# Catch_The_Light_Game.net
KiCad netlist of a schematic drawn in EAGLE
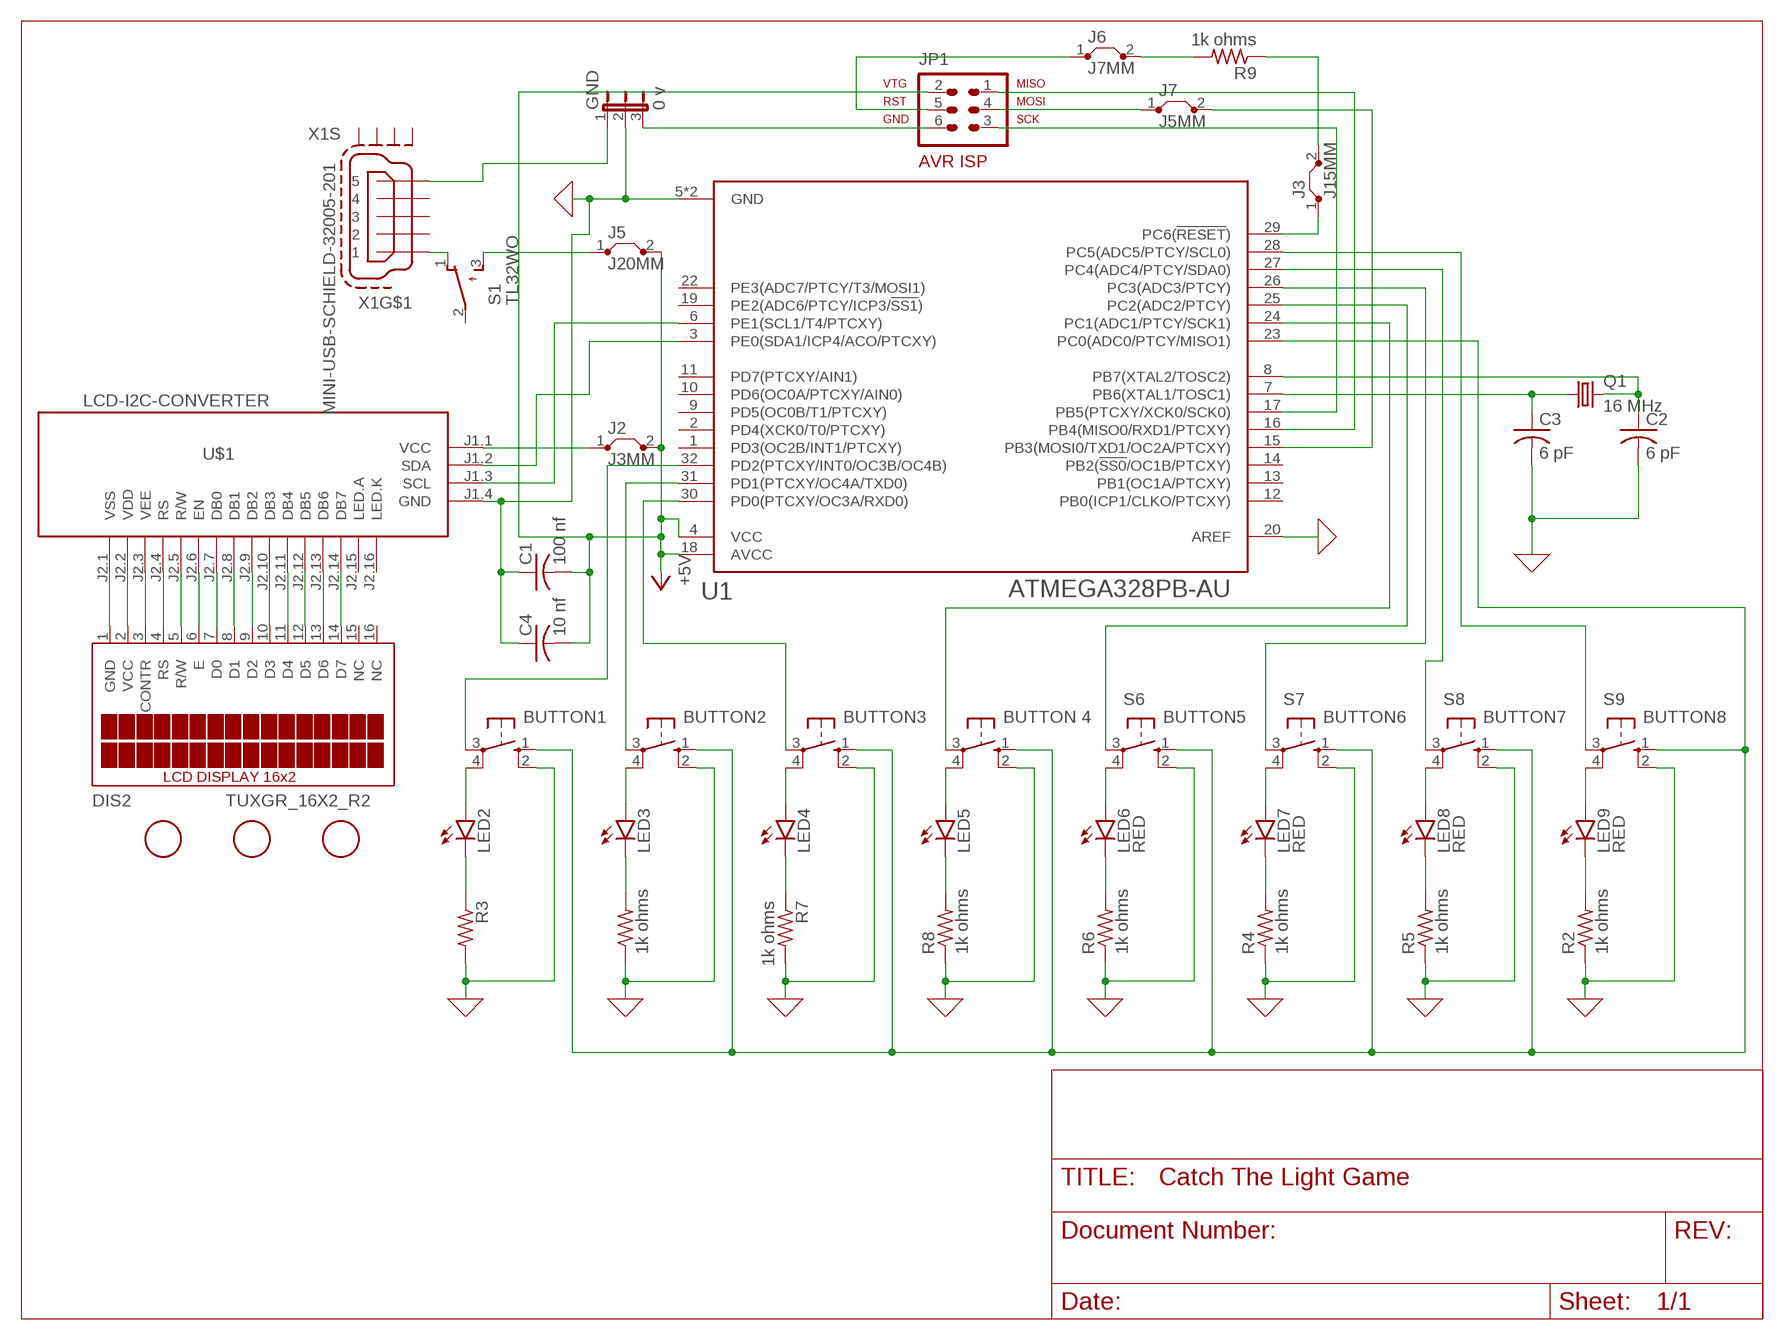
[diagram p0: schematic, sheet 1]

(export (version "E")
  (design (tool "Eeschema 10.0.6"))
  (components
    (comp (ref "C1")
      (value "100 nf")
      (footprint "eagle-import:C025-024X044")
      (libsource (lib "eagle-import") (part "C-US025-024X044"))
    )
    (comp (ref "C2")
      (value "6 pF")
      (footprint "eagle-import:C025-024X044")
      (libsource (lib "eagle-import") (part "C-US025-024X044"))
    )
    (comp (ref "C3")
      (value "6 pF")
      (footprint "eagle-import:C025-024X044")
      (libsource (lib "eagle-import") (part "C-US025-024X044"))
    )
    (comp (ref "C4")
      (value "10 nf")
      (footprint "eagle-import:C025-024X044")
      (libsource (lib "eagle-import") (part "C-US025-024X044"))
    )
    (comp (ref "DIS2")
      (value "TUXGR_16X2_R2")
      (footprint "eagle-import:TUXGR_16X2_R2")
      (fields (field (name "SPICEPREFIX") "X"))
      (libsource (lib "eagle-import") (part "TUXGR_16X2_R2"))
    )
    (comp (ref "GND")
      (value "0 v")
      (footprint "eagle-import:JP2")
      (libsource (lib "eagle-import") (part "JP2E"))
    )
    (comp (ref "J2")
      (value "J3MM")
      (footprint "eagle-import:03")
      (libsource (lib "eagle-import") (part "J3MM"))
    )
    (comp (ref "J3")
      (value "J15MM")
      (footprint "eagle-import:15")
      (libsource (lib "eagle-import") (part "jumper_252_J15MM"))
    )
    (comp (ref "J5")
      (value "J20MM")
      (footprint "eagle-import:20")
      (libsource (lib "eagle-import") (part "jumper_252_J20MM"))
    )
    (comp (ref "J6")
      (value "J7MM")
      (footprint "eagle-import:07")
      (libsource (lib "eagle-import") (part "jumper_252_J7MM"))
    )
    (comp (ref "J7")
      (value "J5MM")
      (footprint "eagle-import:05")
      (libsource (lib "eagle-import") (part "jumper_252_J5MM"))
    )
    (comp (ref "JP1")
      (value "AVR-ISP-6R")
      (footprint "eagle-import:AVR-ISP-6R")
      (libsource (lib "eagle-import") (part "AVR-ISP-6R"))
    )
    (comp (ref "LED2")
      (value "RED")
      (footprint "eagle-import:LED5MM")
      (libsource (lib "eagle-import") (part "LED5MM"))
    )
    (comp (ref "LED3")
      (value "RED")
      (footprint "eagle-import:LED5MM")
      (libsource (lib "eagle-import") (part "LED5MM"))
    )
    (comp (ref "LED4")
      (value "RED")
      (footprint "eagle-import:LED5MM")
      (libsource (lib "eagle-import") (part "LED5MM"))
    )
    (comp (ref "LED5")
      (value "RED")
      (footprint "eagle-import:LED5MM")
      (libsource (lib "eagle-import") (part "LED5MM"))
    )
    (comp (ref "LED6")
      (value "RED")
      (footprint "eagle-import:LED5MM")
      (libsource (lib "eagle-import") (part "LED5MM"))
    )
    (comp (ref "LED7")
      (value "RED")
      (footprint "eagle-import:LED5MM")
      (libsource (lib "eagle-import") (part "LED5MM"))
    )
    (comp (ref "LED8")
      (value "RED")
      (footprint "eagle-import:LED5MM")
      (libsource (lib "eagle-import") (part "LED5MM"))
    )
    (comp (ref "LED9")
      (value "RED")
      (footprint "eagle-import:LED5MM")
      (libsource (lib "eagle-import") (part "LED5MM"))
    )
    (comp (ref "Q1")
      (value "16 MHz")
      (footprint "eagle-import:HC49_S")
      (libsource (lib "eagle-import") (part "CRYSTALHC49S"))
    )
    (comp (ref "R1")
      (value "1k ohms")
      (footprint "eagle-import:0204_5")
      (libsource (lib "eagle-import") (part "R-US_0204/5"))
    )
    (comp (ref "R2")
      (value "1k ohms")
      (footprint "eagle-import:0204_5")
      (libsource (lib "eagle-import") (part "R-US_0204/5"))
    )
    (comp (ref "R3")
      (value "1K ohms")
      (footprint "eagle-import:0204_5")
      (libsource (lib "eagle-import") (part "R-US_0204/5"))
    )
    (comp (ref "R4")
      (value "1k ohms")
      (footprint "eagle-import:0204_5")
      (libsource (lib "eagle-import") (part "R-US_0204/5"))
    )
    (comp (ref "R5")
      (value "1k ohms")
      (footprint "eagle-import:0204_5")
      (libsource (lib "eagle-import") (part "R-US_0204/5"))
    )
    (comp (ref "R6")
      (value "1k ohms")
      (footprint "eagle-import:0204_5")
      (libsource (lib "eagle-import") (part "R-US_0204/5"))
    )
    (comp (ref "R7")
      (value "1k ohms")
      (footprint "eagle-import:0204_5")
      (libsource (lib "eagle-import") (part "R-US_0204/5"))
    )
    (comp (ref "R8")
      (value "1k ohms")
      (footprint "eagle-import:0204_5")
      (libsource (lib "eagle-import") (part "R-US_0204/5"))
    )
    (comp (ref "R9")
      (value "1k ohms")
      (footprint "eagle-import:0204_5")
      (libsource (lib "eagle-import") (part "R-US_0204/5"))
    )
    (comp (ref "S1")
      (value "TL32WO")
      (footprint "eagle-import:TL3XWO")
      (libsource (lib "eagle-import") (part "TL32WO"))
    )
    (comp (ref "S2")
      (value "BUTTON1")
      (footprint "eagle-import:B3F-10XX")
      (fields (field (name "MPN") "B3F-1000"))
      (libsource (lib "eagle-import") (part "10-XX"))
    )
    (comp (ref "S3")
      (value "BUTTON2")
      (footprint "eagle-import:B3F-10XX")
      (fields (field (name "MPN") "B3F-1000"))
      (libsource (lib "eagle-import") (part "10-XX"))
    )
    (comp (ref "S4")
      (value "BUTTON3")
      (footprint "eagle-import:B3F-10XX")
      (fields (field (name "MPN") "B3F-1000"))
      (libsource (lib "eagle-import") (part "10-XX"))
    )
    (comp (ref "S5")
      (value "BUTTON 4")
      (footprint "eagle-import:B3F-10XX")
      (fields (field (name "MPN") "B3F-1000"))
      (libsource (lib "eagle-import") (part "10-XX"))
    )
    (comp (ref "S6")
      (value "BUTTON5")
      (footprint "eagle-import:B3F-10XX")
      (fields (field (name "MPN") "B3F-1000"))
      (libsource (lib "eagle-import") (part "10-XX"))
    )
    (comp (ref "S7")
      (value "BUTTON6")
      (footprint "eagle-import:B3F-10XX")
      (fields (field (name "MPN") "B3F-1000"))
      (libsource (lib "eagle-import") (part "10-XX"))
    )
    (comp (ref "S8")
      (value "BUTTON7")
      (footprint "eagle-import:B3F-10XX")
      (fields (field (name "MPN") "B3F-1000"))
      (libsource (lib "eagle-import") (part "10-XX"))
    )
    (comp (ref "S9")
      (value "BUTTON8")
      (footprint "eagle-import:B3F-10XX")
      (fields (field (name "MPN") "B3F-1000"))
      (libsource (lib "eagle-import") (part "10-XX"))
    )
    (comp (ref "U$1")
      (value "LCD-I2C-CONVERTER")
      (footprint "eagle-import:LCD-I2C-CONVERTER")
      (fields (field (name "SPICEPREFIX") "X"))
      (libsource (lib "eagle-import") (part "LCD-I2C-CONVERTER"))
    )
    (comp (ref "U$2")
      (value "FIDUCIAL")
      (footprint "eagle-import:FIDUCIAL_1MM")
      (libsource (lib "eagle-import") (part "FIDUCIAL"))
    )
    (comp (ref "U$3")
      (value "FIDUCIAL")
      (footprint "eagle-import:FIDUCIAL_1MM")
      (libsource (lib "eagle-import") (part "FIDUCIAL"))
    )
    (comp (ref "U$4")
      (value "FIDUCIAL")
      (footprint "eagle-import:FIDUCIAL_1MM")
      (libsource (lib "eagle-import") (part "FIDUCIAL"))
    )
    (comp (ref "U1")
      (value "ATMEGA328PB-AU")
      (footprint "eagle-import:QFP80P900X900X120-32N")
      (fields (field (name "MF") "Microchip Technology"))
      (libsource (lib "eagle-import") (part "ATMEGA328PB-AU"))
    )
    (comp (ref "X1")
      (value "MINI-USB-SCHIELD-32005-201")
      (footprint "eagle-import:32005-201")
      (libsource (lib "eagle-import") (part "MINI-USB-SCHIELD-32005-201"))
    )
  )
  (nets
    (net (code "1") (name "+5V") (class "Default")
      (node (ref "C1") (pin "2") (pinfunction "2_2") (pintype "passive"))
      (node (ref "C4") (pin "2") (pinfunction "2_2") (pintype "passive"))
      (node (ref "J2") (pin "2") (pinfunction "2_2") (pintype "passive"))
      (node (ref "J5") (pin "2") (pinfunction "2_2") (pintype "passive"))
      (node (ref "JP1") (pin "2") (pinfunction "2_2") (pintype "passive"))
      (node (ref "U1") (pin "18") (pinfunction "AVCC_18") (pintype "power_in"))
      (node (ref "U1") (pin "4") (pinfunction "VCC_4") (pintype "power_in"))
    )
    (net (code "2") (name "GND") (class "Default")
      (node (ref "C1") (pin "1") (pinfunction "1_1") (pintype "passive"))
      (node (ref "C2") (pin "2") (pinfunction "2_2") (pintype "passive"))
      (node (ref "C3") (pin "2") (pinfunction "2_2") (pintype "passive"))
      (node (ref "C4") (pin "1") (pinfunction "1_1") (pintype "passive"))
      (node (ref "GND") (pin "2") (pinfunction "2_2") (pintype "passive"))
      (node (ref "R1") (pin "1") (pinfunction "1_1") (pintype "passive"))
      (node (ref "R2") (pin "1") (pinfunction "1_1") (pintype "passive"))
      (node (ref "R3") (pin "2") (pinfunction "2_2") (pintype "passive"))
      (node (ref "R4") (pin "1") (pinfunction "1_1") (pintype "passive"))
      (node (ref "R5") (pin "1") (pinfunction "1_1") (pintype "passive"))
      (node (ref "R6") (pin "1") (pinfunction "1_1") (pintype "passive"))
      (node (ref "R7") (pin "2") (pinfunction "2_2") (pintype "passive"))
      (node (ref "R8") (pin "1") (pinfunction "1_1") (pintype "passive"))
      (node (ref "S2") (pin "2") (pinfunction "S1_2") (pintype "passive"))
      (node (ref "S3") (pin "2") (pinfunction "S1_2") (pintype "passive"))
      (node (ref "S4") (pin "2") (pinfunction "S1_2") (pintype "passive"))
      (node (ref "S5") (pin "2") (pinfunction "S1_2") (pintype "passive"))
      (node (ref "S6") (pin "2") (pinfunction "S1_2") (pintype "passive"))
      (node (ref "S7") (pin "2") (pinfunction "S1_2") (pintype "passive"))
      (node (ref "S8") (pin "2") (pinfunction "S1_2") (pintype "passive"))
      (node (ref "S9") (pin "2") (pinfunction "S1_2") (pintype "passive"))
      (node (ref "U$1") (pin "J1.4") (pinfunction "GND_J1.4") (pintype "power_in"))
      (node (ref "U1") (pin "20") (pinfunction "AREF_20") (pintype "input"))
      (node (ref "U1") (pin "21") (pinfunction "GND_21") (pintype "power_in"))
      (node (ref "U1") (pin "5") (pinfunction "GND_5") (pintype "power_in"))
    )
    (net (code "3") (name "Net-(DIS2-CONTR)") (class "Default")
      (node (ref "DIS2") (pin "3") (pinfunction "CONTR_3") (pintype "input"))
      (node (ref "U$1") (pin "J2.3") (pinfunction "VEE_J2.3") (pintype "bidirectional"))
    )
    (net (code "4") (name "Net-(DIS2-D0)") (class "Default")
      (node (ref "DIS2") (pin "7") (pinfunction "D0_7") (pintype "input"))
      (node (ref "U$1") (pin "J2.7") (pinfunction "DB0_J2.7") (pintype "bidirectional"))
    )
    (net (code "5") (name "Net-(DIS2-D1)") (class "Default")
      (node (ref "DIS2") (pin "8") (pinfunction "D1_8") (pintype "input"))
      (node (ref "U$1") (pin "J2.8") (pinfunction "DB1_J2.8") (pintype "bidirectional"))
    )
    (net (code "6") (name "Net-(DIS2-D2)") (class "Default")
      (node (ref "DIS2") (pin "9") (pinfunction "D2_9") (pintype "input"))
      (node (ref "U$1") (pin "J2.9") (pinfunction "DB2_J2.9") (pintype "bidirectional"))
    )
    (net (code "7") (name "Net-(DIS2-D3)") (class "Default")
      (node (ref "DIS2") (pin "10") (pinfunction "D3_10") (pintype "input"))
      (node (ref "U$1") (pin "J2.10") (pinfunction "DB3_J2.10") (pintype "bidirectional"))
    )
    (net (code "8") (name "Net-(DIS2-D4)") (class "Default")
      (node (ref "DIS2") (pin "11") (pinfunction "D4_11") (pintype "input"))
      (node (ref "U$1") (pin "J2.11") (pinfunction "DB4_J2.11") (pintype "bidirectional"))
    )
    (net (code "9") (name "Net-(DIS2-D5)") (class "Default")
      (node (ref "DIS2") (pin "12") (pinfunction "D5_12") (pintype "input"))
      (node (ref "U$1") (pin "J2.12") (pinfunction "DB5_J2.12") (pintype "bidirectional"))
    )
    (net (code "10") (name "Net-(DIS2-D6)") (class "Default")
      (node (ref "DIS2") (pin "13") (pinfunction "D6_13") (pintype "input"))
      (node (ref "U$1") (pin "J2.13") (pinfunction "DB6_J2.13") (pintype "bidirectional"))
    )
    (net (code "11") (name "Net-(DIS2-D7)") (class "Default")
      (node (ref "DIS2") (pin "14") (pinfunction "D7_14") (pintype "input"))
      (node (ref "U$1") (pin "J2.14") (pinfunction "DB7_J2.14") (pintype "bidirectional"))
    )
    (net (code "12") (name "Net-(DIS2-E)") (class "Default")
      (node (ref "DIS2") (pin "6") (pinfunction "E_6") (pintype "input"))
      (node (ref "U$1") (pin "J2.6") (pinfunction "EN_J2.6") (pintype "bidirectional"))
    )
    (net (code "13") (name "Net-(DIS2-GND)") (class "Default")
      (node (ref "DIS2") (pin "1") (pinfunction "GND_1") (pintype "power_in"))
      (node (ref "U$1") (pin "J2.1") (pinfunction "VSS_J2.1") (pintype "bidirectional"))
    )
    (net (code "14") (name "Net-(DIS2-RS)") (class "Default")
      (node (ref "DIS2") (pin "4") (pinfunction "RS_4") (pintype "input"))
      (node (ref "U$1") (pin "J2.4") (pinfunction "RS_J2.4") (pintype "bidirectional"))
    )
    (net (code "15") (name "Net-(DIS2-R{slash}W)") (class "Default")
      (node (ref "DIS2") (pin "5") (pinfunction "R/W_5") (pintype "input"))
      (node (ref "U$1") (pin "J2.5") (pinfunction "R/W_J2.5") (pintype "bidirectional"))
    )
    (net (code "16") (name "Net-(DIS2-VCC)") (class "Default")
      (node (ref "DIS2") (pin "2") (pinfunction "VCC_2") (pintype "power_in"))
      (node (ref "U$1") (pin "J2.2") (pinfunction "VDD_J2.2") (pintype "bidirectional"))
    )
    (net (code "17") (name "Net-(GND-Pad1)") (class "Default")
      (node (ref "GND") (pin "1") (pinfunction "1_1") (pintype "passive"))
      (node (ref "X1") (pin "5") (pinfunction "5_5") (pintype "passive"))
    )
    (net (code "18") (name "Net-(GND-Pad3)") (class "Default")
      (node (ref "GND") (pin "3") (pinfunction "3_3") (pintype "passive"))
      (node (ref "JP1") (pin "6") (pinfunction "6_6") (pintype "passive"))
    )
    (net (code "19") (name "Net-(J3-Pad2)") (class "Default")
      (node (ref "J3") (pin "2") (pinfunction "2_2") (pintype "passive"))
      (node (ref "R9") (pin "1") (pinfunction "1_1") (pintype "passive"))
    )
    (net (code "20") (name "Net-(J6-Pad1)") (class "Default")
      (node (ref "J6") (pin "1") (pinfunction "1_1") (pintype "passive"))
      (node (ref "JP1") (pin "5") (pinfunction "5_5") (pintype "passive"))
    )
    (net (code "21") (name "Net-(J6-Pad2)") (class "Default")
      (node (ref "J6") (pin "2") (pinfunction "2_2") (pintype "passive"))
      (node (ref "R9") (pin "2") (pinfunction "2_2") (pintype "passive"))
    )
    (net (code "22") (name "Net-(J7-Pad1)") (class "Default")
      (node (ref "J7") (pin "1") (pinfunction "1_1") (pintype "passive"))
      (node (ref "JP1") (pin "4") (pinfunction "4_4") (pintype "passive"))
    )
    (net (code "23") (name "Net-(LED2-C)") (class "Default")
      (node (ref "LED2") (pin "K") (pinfunction "C_K") (pintype "passive"))
      (node (ref "R3") (pin "1") (pinfunction "1_1") (pintype "passive"))
    )
    (net (code "24") (name "Net-(LED3-C)") (class "Default")
      (node (ref "LED3") (pin "K") (pinfunction "C_K") (pintype "passive"))
      (node (ref "R1") (pin "2") (pinfunction "2_2") (pintype "passive"))
    )
    (net (code "25") (name "Net-(LED4-C)") (class "Default")
      (node (ref "LED4") (pin "K") (pinfunction "C_K") (pintype "passive"))
      (node (ref "R7") (pin "1") (pinfunction "1_1") (pintype "passive"))
    )
    (net (code "26") (name "Net-(LED5-C)") (class "Default")
      (node (ref "LED5") (pin "K") (pinfunction "C_K") (pintype "passive"))
      (node (ref "R8") (pin "2") (pinfunction "2_2") (pintype "passive"))
    )
    (net (code "27") (name "Net-(LED6-C)") (class "Default")
      (node (ref "LED6") (pin "K") (pinfunction "C_K") (pintype "passive"))
      (node (ref "R6") (pin "2") (pinfunction "2_2") (pintype "passive"))
    )
    (net (code "28") (name "Net-(LED7-C)") (class "Default")
      (node (ref "LED7") (pin "K") (pinfunction "C_K") (pintype "passive"))
      (node (ref "R4") (pin "2") (pinfunction "2_2") (pintype "passive"))
    )
    (net (code "29") (name "Net-(LED8-C)") (class "Default")
      (node (ref "LED8") (pin "K") (pinfunction "C_K") (pintype "passive"))
      (node (ref "R5") (pin "2") (pinfunction "2_2") (pintype "passive"))
    )
    (net (code "30") (name "Net-(LED9-C)") (class "Default")
      (node (ref "LED9") (pin "K") (pinfunction "C_K") (pintype "passive"))
      (node (ref "R2") (pin "2") (pinfunction "2_2") (pintype "passive"))
    )
    (net (code "31") (name "Net-(S1-O)") (class "Default")
      (node (ref "S1") (pin "1") (pinfunction "O_1") (pintype "passive"))
      (node (ref "X1") (pin "1") (pinfunction "1_1") (pintype "passive"))
    )
    (net (code "32") (name "Net-(S1-S)") (class "Default")
      (node (ref "J5") (pin "1") (pinfunction "1_1") (pintype "passive"))
      (node (ref "S1") (pin "3") (pinfunction "S_3") (pintype "passive"))
    )
    (net (code "33") (name "Net-(S2-P)") (class "Default")
      (node (ref "S2") (pin "3") (pinfunction "P_3") (pintype "passive"))
      (node (ref "U1") (pin "32") (pinfunction "PD2(PTCXY/INT0/OC3B/OC4B)_32") (pintype "bidirectional"))
    )
    (net (code "34") (name "Net-(S2-P1)") (class "Default")
      (node (ref "LED2") (pin "A") (pinfunction "A_A") (pintype "passive"))
      (node (ref "S2") (pin "4") (pinfunction "P1_4") (pintype "passive"))
    )
    (net (code "35") (name "Net-(S2-S)") (class "Default")
      (node (ref "S2") (pin "1") (pinfunction "S_1") (pintype "passive"))
      (node (ref "S3") (pin "1") (pinfunction "S_1") (pintype "passive"))
      (node (ref "S4") (pin "1") (pinfunction "S_1") (pintype "passive"))
      (node (ref "S5") (pin "1") (pinfunction "S_1") (pintype "passive"))
      (node (ref "S6") (pin "1") (pinfunction "S_1") (pintype "passive"))
      (node (ref "S7") (pin "1") (pinfunction "S_1") (pintype "passive"))
      (node (ref "S8") (pin "1") (pinfunction "S_1") (pintype "passive"))
      (node (ref "S9") (pin "1") (pinfunction "S_1") (pintype "passive"))
      (node (ref "U1") (pin "23") (pinfunction "PC0(ADC0/PTCY/MISO1)_23") (pintype "bidirectional"))
    )
    (net (code "36") (name "Net-(S3-P)") (class "Default")
      (node (ref "S3") (pin "3") (pinfunction "P_3") (pintype "passive"))
      (node (ref "U1") (pin "31") (pinfunction "PD1(PTCXY/OC4A/TXD0)_31") (pintype "bidirectional"))
    )
    (net (code "37") (name "Net-(S3-P1)") (class "Default")
      (node (ref "LED3") (pin "A") (pinfunction "A_A") (pintype "passive"))
      (node (ref "S3") (pin "4") (pinfunction "P1_4") (pintype "passive"))
    )
    (net (code "38") (name "Net-(S4-P)") (class "Default")
      (node (ref "S4") (pin "3") (pinfunction "P_3") (pintype "passive"))
      (node (ref "U1") (pin "30") (pinfunction "PD0(PTCXY/OC3A/RXD0)_30") (pintype "bidirectional"))
    )
    (net (code "39") (name "Net-(S4-P1)") (class "Default")
      (node (ref "LED4") (pin "A") (pinfunction "A_A") (pintype "passive"))
      (node (ref "S4") (pin "4") (pinfunction "P1_4") (pintype "passive"))
    )
    (net (code "40") (name "Net-(S5-P)") (class "Default")
      (node (ref "S5") (pin "3") (pinfunction "P_3") (pintype "passive"))
      (node (ref "U1") (pin "24") (pinfunction "PC1(ADC1/PTCY/SCK1)_24") (pintype "bidirectional"))
    )
    (net (code "41") (name "Net-(S5-P1)") (class "Default")
      (node (ref "LED5") (pin "A") (pinfunction "A_A") (pintype "passive"))
      (node (ref "S5") (pin "4") (pinfunction "P1_4") (pintype "passive"))
    )
    (net (code "42") (name "Net-(S6-P)") (class "Default")
      (node (ref "S6") (pin "3") (pinfunction "P_3") (pintype "passive"))
      (node (ref "U1") (pin "25") (pinfunction "PC2(ADC2/PTCY)_25") (pintype "bidirectional"))
    )
    (net (code "43") (name "Net-(S6-P1)") (class "Default")
      (node (ref "LED6") (pin "A") (pinfunction "A_A") (pintype "passive"))
      (node (ref "S6") (pin "4") (pinfunction "P1_4") (pintype "passive"))
    )
    (net (code "44") (name "Net-(S7-P)") (class "Default")
      (node (ref "S7") (pin "3") (pinfunction "P_3") (pintype "passive"))
      (node (ref "U1") (pin "26") (pinfunction "PC3(ADC3/PTCY)_26") (pintype "bidirectional"))
    )
    (net (code "45") (name "Net-(S7-P1)") (class "Default")
      (node (ref "LED7") (pin "A") (pinfunction "A_A") (pintype "passive"))
      (node (ref "S7") (pin "4") (pinfunction "P1_4") (pintype "passive"))
    )
    (net (code "46") (name "Net-(S8-P)") (class "Default")
      (node (ref "S8") (pin "3") (pinfunction "P_3") (pintype "passive"))
      (node (ref "U1") (pin "27") (pinfunction "PC4(ADC4/PTCY/SDA0)_27") (pintype "bidirectional"))
    )
    (net (code "47") (name "Net-(S8-P1)") (class "Default")
      (node (ref "LED8") (pin "A") (pinfunction "A_A") (pintype "passive"))
      (node (ref "S8") (pin "4") (pinfunction "P1_4") (pintype "passive"))
    )
    (net (code "48") (name "Net-(S9-P)") (class "Default")
      (node (ref "S9") (pin "3") (pinfunction "P_3") (pintype "passive"))
      (node (ref "U1") (pin "28") (pinfunction "PC5(ADC5/PTCY/SCL0)_28") (pintype "bidirectional"))
    )
    (net (code "49") (name "Net-(S9-P1)") (class "Default")
      (node (ref "LED9") (pin "A") (pinfunction "A_A") (pintype "passive"))
      (node (ref "S9") (pin "4") (pinfunction "P1_4") (pintype "passive"))
    )
    (net (code "50") (name "Net-(U$1-SCL)") (class "Default")
      (node (ref "U$1") (pin "J1.3") (pinfunction "SCL_J1.3") (pintype "bidirectional"))
      (node (ref "U1") (pin "6") (pinfunction "PE1(SCL1/T4/PTCXY)_6") (pintype "bidirectional"))
    )
    (net (code "51") (name "Net-(U$1-SDA)") (class "Default")
      (node (ref "U$1") (pin "J1.2") (pinfunction "SDA_J1.2") (pintype "bidirectional"))
      (node (ref "U1") (pin "3") (pinfunction "PE0(SDA1/ICP4/ACO/PTCXY)_3") (pintype "bidirectional"))
    )
    (net (code "52") (name "Net-(U$1-VCC)") (class "Default")
      (node (ref "J2") (pin "1") (pinfunction "1_1") (pintype "passive"))
      (node (ref "U$1") (pin "J1.1") (pinfunction "VCC_J1.1") (pintype "power_in"))
    )
    (net (code "53") (name "Net-(U1-PB3(MOSI0{slash}TXD1{slash}OC2A{slash}PTCXY))") (class "Default")
      (node (ref "J7") (pin "2") (pinfunction "2_2") (pintype "passive"))
      (node (ref "U1") (pin "15") (pinfunction "PB3(MOSI0/TXD1/OC2A/PTCXY)_15") (pintype "bidirectional"))
    )
    (net (code "54") (name "Net-(U1-PB4(MISO0{slash}RXD1{slash}PTCXY))") (class "Default")
      (node (ref "JP1") (pin "1") (pinfunction "1_1") (pintype "passive"))
      (node (ref "U1") (pin "16") (pinfunction "PB4(MISO0/RXD1/PTCXY)_16") (pintype "bidirectional"))
    )
    (net (code "55") (name "Net-(U1-PB5(PTCXY{slash}XCK0{slash}SCK0))") (class "Default")
      (node (ref "JP1") (pin "3") (pinfunction "3_3") (pintype "passive"))
      (node (ref "U1") (pin "17") (pinfunction "PB5(PTCXY/XCK0/SCK0)_17") (pintype "bidirectional"))
    )
    (net (code "56") (name "Net-(U1-PB6(XTAL1{slash}TOSC1))") (class "Default")
      (node (ref "C3") (pin "1") (pinfunction "1_1") (pintype "passive"))
      (node (ref "Q1") (pin "1") (pinfunction "1_1") (pintype "passive"))
      (node (ref "U1") (pin "7") (pinfunction "PB6(XTAL1/TOSC1)_7") (pintype "bidirectional"))
    )
    (net (code "57") (name "Net-(U1-PB7(XTAL2{slash}TOSC2))") (class "Default")
      (node (ref "C2") (pin "1") (pinfunction "1_1") (pintype "passive"))
      (node (ref "Q1") (pin "2") (pinfunction "2_2") (pintype "passive"))
      (node (ref "U1") (pin "8") (pinfunction "PB7(XTAL2/TOSC2)_8") (pintype "bidirectional"))
    )
    (net (code "58") (name "Net-(U1-PC6(~{RESET}))") (class "Default")
      (node (ref "J3") (pin "1") (pinfunction "1_1") (pintype "passive"))
      (node (ref "U1") (pin "29") (pinfunction "PC6(~{RESET})_29") (pintype "bidirectional"))
    )
    (net (code "59") (name "unconnected-(DIS2-NC-Pad15)") (class "Default")
      (node (ref "DIS2") (pin "15") (pinfunction "NC_15") (pintype "no_connect"))
    )
    (net (code "60") (name "unconnected-(DIS2-NC-Pad16)") (class "Default")
      (node (ref "DIS2") (pin "16") (pinfunction "NC_16") (pintype "no_connect"))
    )
    (net (code "61") (name "unconnected-(S1-P-Pad2)") (class "Default")
      (node (ref "S1") (pin "2") (pinfunction "P_2") (pintype "passive"))
    )
    (net (code "62") (name "unconnected-(U$1-LED.A-PadJ2.15)") (class "Default")
      (node (ref "U$1") (pin "J2.15") (pinfunction "LED.A_J2.15") (pintype "bidirectional"))
    )
    (net (code "63") (name "unconnected-(U$1-LED.K-PadJ2.16)") (class "Default")
      (node (ref "U$1") (pin "J2.16") (pinfunction "LED.K_J2.16") (pintype "bidirectional"))
    )
    (net (code "64") (name "unconnected-(U1-PB0(ICP1{slash}CLKO{slash}PTCXY)-Pad12)") (class "Default")
      (node (ref "U1") (pin "12") (pinfunction "PB0(ICP1/CLKO/PTCXY)_12") (pintype "bidirectional"))
    )
    (net (code "65") (name "unconnected-(U1-PB1(OC1A{slash}PTCXY)-Pad13)") (class "Default")
      (node (ref "U1") (pin "13") (pinfunction "PB1(OC1A/PTCXY)_13") (pintype "bidirectional"))
    )
    (net (code "66") (name "unconnected-(U1-PB2(~{SS0}{slash}OC1B{slash}PTCXY)-Pad14)") (class "Default")
      (node (ref "U1") (pin "14") (pinfunction "PB2(~{SS0}/OC1B/PTCXY)_14") (pintype "bidirectional"))
    )
    (net (code "67") (name "unconnected-(U1-PD3(OC2B{slash}INT1{slash}PTCXY)-Pad1)") (class "Default")
      (node (ref "U1") (pin "1") (pinfunction "PD3(OC2B/INT1/PTCXY)_1") (pintype "bidirectional"))
    )
    (net (code "68") (name "unconnected-(U1-PD4(XCK0{slash}T0{slash}PTCXY)-Pad2)") (class "Default")
      (node (ref "U1") (pin "2") (pinfunction "PD4(XCK0/T0/PTCXY)_2") (pintype "bidirectional"))
    )
    (net (code "69") (name "unconnected-(U1-PD5(OC0B{slash}T1{slash}PTCXY)-Pad9)") (class "Default")
      (node (ref "U1") (pin "9") (pinfunction "PD5(OC0B/T1/PTCXY)_9") (pintype "bidirectional"))
    )
    (net (code "70") (name "unconnected-(U1-PD6(OC0A{slash}PTCXY{slash}AIN0)-Pad10)") (class "Default")
      (node (ref "U1") (pin "10") (pinfunction "PD6(OC0A/PTCXY/AIN0)_10") (pintype "bidirectional"))
    )
    (net (code "71") (name "unconnected-(U1-PD7(PTCXY{slash}AIN1)-Pad11)") (class "Default")
      (node (ref "U1") (pin "11") (pinfunction "PD7(PTCXY/AIN1)_11") (pintype "bidirectional"))
    )
    (net (code "72") (name "unconnected-(U1-PE2(ADC6{slash}PTCY{slash}ICP3{slash}~{SS1})-Pad19)") (class "Default")
      (node (ref "U1") (pin "19") (pinfunction "PE2(ADC6/PTCY/ICP3/~{SS1})_19") (pintype "bidirectional"))
    )
    (net (code "73") (name "unconnected-(U1-PE3(ADC7{slash}PTCY{slash}T3{slash}MOSI1)-Pad22)") (class "Default")
      (node (ref "U1") (pin "22") (pinfunction "PE3(ADC7/PTCY/T3/MOSI1)_22") (pintype "bidirectional"))
    )
    (net (code "74") (name "unconnected-(X1-Pad2)") (class "Default")
      (node (ref "X1") (pin "2") (pinfunction "2_2") (pintype "passive"))
    )
    (net (code "75") (name "unconnected-(X1-Pad3)") (class "Default")
      (node (ref "X1") (pin "3") (pinfunction "3_3") (pintype "passive"))
    )
    (net (code "76") (name "unconnected-(X1-Pad4)") (class "Default")
      (node (ref "X1") (pin "4") (pinfunction "4_4") (pintype "passive"))
    )
    (net (code "77") (name "unconnected-(X1B-S1-PadM1)") (class "Default")
      (node (ref "X1") (pin "M1") (pinfunction "S1_M1") (pintype "passive"))
    )
    (net (code "78") (name "unconnected-(X1B-S2-PadM2)") (class "Default")
      (node (ref "X1") (pin "M2") (pinfunction "S2_M2") (pintype "passive"))
    )
    (net (code "79") (name "unconnected-(X1B-S3-PadM3)") (class "Default")
      (node (ref "X1") (pin "M3") (pinfunction "S3_M3") (pintype "passive"))
    )
    (net (code "80") (name "unconnected-(X1B-S4-PadM4)") (class "Default")
      (node (ref "X1") (pin "M4") (pinfunction "S4_M4") (pintype "passive"))
    )
  )
)
